# rpi_hat.net
KiCad netlist of a schematic drawn in EAGLE
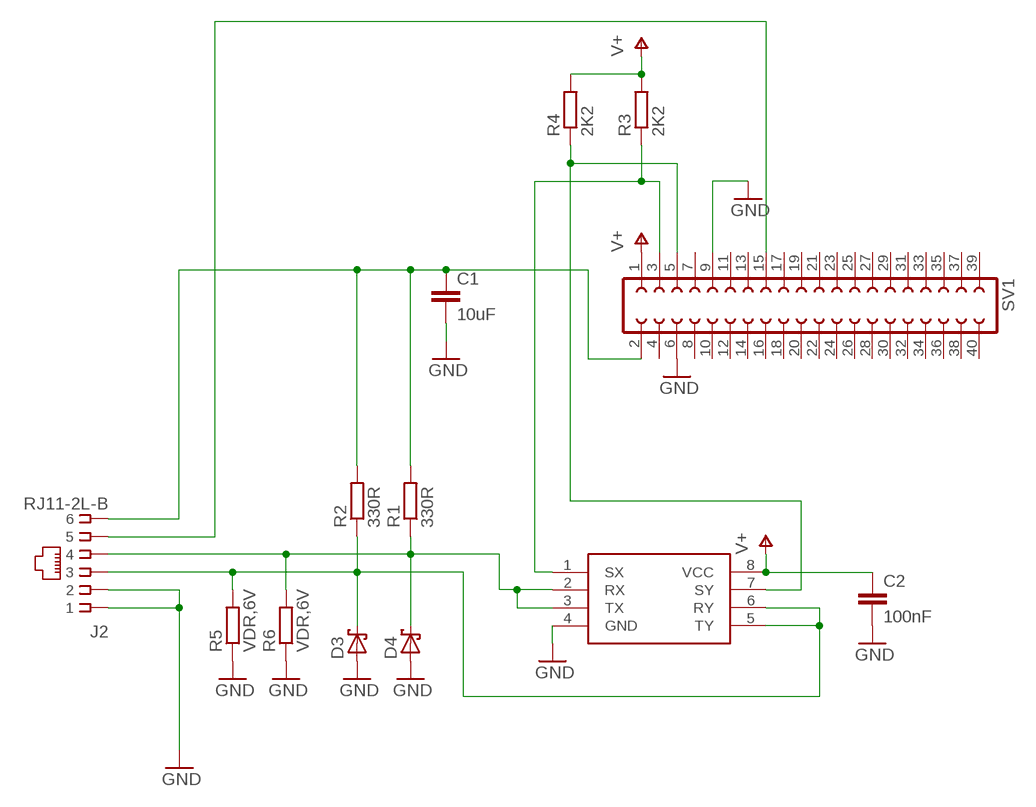
[diagram p0: schematic, sheet 1]

(export (version "E")
  (design (tool "Eeschema 10.0.6"))
  (components
    (comp (ref "C1")
      (value "10uF")
      (footprint "eagle-import:C0805")
      (libsource (lib "eagle-import") (part "C-EUC0805"))
    )
    (comp (ref "C2")
      (value "100nF")
      (footprint "eagle-import:C0805")
      (libsource (lib "eagle-import") (part "C-EUC0805"))
    )
    (comp (ref "D3")
      (value "SCHOTTKY-DIODE")
      (footprint "eagle-import:DIODE_SMB")
      (libsource (lib "eagle-import") (part "SCHOTTKY-DIODE"))
    )
    (comp (ref "D4")
      (value "SCHOTTKY-DIODE")
      (footprint "eagle-import:DIODE_SMB")
      (libsource (lib "eagle-import") (part "SCHOTTKY-DIODE"))
    )
    (comp (ref "J2")
      (value "RJ11-2L-B")
      (footprint "eagle-import:RJ11-NO_SHIELD")
      (fields (field (name "MF") "TYCO ELECTRONICS"))
      (libsource (lib "eagle-import") (part "RJ11-2L-B"))
    )
    (comp (ref "R1")
      (value "330R")
      (footprint "eagle-import:R0805")
      (libsource (lib "eagle-import") (part "R-EU_R0805"))
    )
    (comp (ref "R2")
      (value "330R")
      (footprint "eagle-import:R0805")
      (libsource (lib "eagle-import") (part "R-EU_R0805"))
    )
    (comp (ref "R3")
      (value "2K2")
      (footprint "eagle-import:R0805")
      (libsource (lib "eagle-import") (part "R-EU_R0805"))
    )
    (comp (ref "R4")
      (value "2K2")
      (footprint "eagle-import:R0805")
      (libsource (lib "eagle-import") (part "R-EU_R0805"))
    )
    (comp (ref "R5")
      (value "VDR,6V")
      (footprint "eagle-import:R1206")
      (libsource (lib "eagle-import") (part "R-EU_R1206"))
    )
    (comp (ref "R6")
      (value "VDR,6V")
      (footprint "eagle-import:R1206")
      (libsource (lib "eagle-import") (part "R-EU_R1206"))
    )
    (comp (ref "SV1")
      (value "FE20-2")
      (footprint "eagle-import:FE20-2")
      (libsource (lib "eagle-import") (part "FE20-2"))
    )
    (comp (ref "U$2")
      (value "P82B96")
      (footprint "eagle-import:DIP8")
      (libsource (lib "eagle-import") (part "P82B96"))
    )
  )
  (nets
    (net (code "1") (name "GND") (class "Default")
      (node (ref "C1") (pin "2") (pinfunction "2_2") (pintype "passive"))
      (node (ref "C2") (pin "2") (pinfunction "2_2") (pintype "passive"))
      (node (ref "D3") (pin "A") (pinfunction "C_A") (pintype "passive"))
      (node (ref "D4") (pin "A") (pinfunction "C_A") (pintype "passive"))
      (node (ref "J2") (pin "1") (pinfunction "1_1") (pintype "passive"))
      (node (ref "J2") (pin "2") (pinfunction "2_2") (pintype "passive"))
      (node (ref "R5") (pin "1") (pinfunction "1_1") (pintype "passive"))
      (node (ref "R6") (pin "1") (pinfunction "1_1") (pintype "passive"))
      (node (ref "SV1") (pin "6") (pinfunction "6_6") (pintype "passive"))
      (node (ref "SV1") (pin "9") (pinfunction "9_9") (pintype "passive"))
      (node (ref "U$2") (pin "4") (pinfunction "GND_4") (pintype "bidirectional"))
    )
    (net (code "2") (name "Net-(C1-Pad1)") (class "Default")
      (node (ref "C1") (pin "1") (pinfunction "1_1") (pintype "passive"))
      (node (ref "J2") (pin "6") (pinfunction "6_6") (pintype "passive"))
      (node (ref "R1") (pin "2") (pinfunction "2_2") (pintype "passive"))
      (node (ref "R2") (pin "2") (pinfunction "2_2") (pintype "passive"))
      (node (ref "SV1") (pin "2") (pinfunction "2_2") (pintype "passive"))
    )
    (net (code "3") (name "Net-(D3-A)") (class "Default")
      (node (ref "D3") (pin "C") (pinfunction "A_C") (pintype "passive"))
      (node (ref "J2") (pin "3") (pinfunction "3_3") (pintype "passive"))
      (node (ref "R2") (pin "1") (pinfunction "1_1") (pintype "passive"))
      (node (ref "R5") (pin "2") (pinfunction "2_2") (pintype "passive"))
      (node (ref "U$2") (pin "5") (pinfunction "TY_5") (pintype "bidirectional"))
      (node (ref "U$2") (pin "6") (pinfunction "RY_6") (pintype "bidirectional"))
    )
    (net (code "4") (name "Net-(D4-A)") (class "Default")
      (node (ref "D4") (pin "C") (pinfunction "A_C") (pintype "passive"))
      (node (ref "J2") (pin "4") (pinfunction "4_4") (pintype "passive"))
      (node (ref "R1") (pin "1") (pinfunction "1_1") (pintype "passive"))
      (node (ref "R6") (pin "2") (pinfunction "2_2") (pintype "passive"))
      (node (ref "U$2") (pin "2") (pinfunction "RX_2") (pintype "bidirectional"))
      (node (ref "U$2") (pin "3") (pinfunction "TX_3") (pintype "bidirectional"))
    )
    (net (code "5") (name "Net-(J2-Pad5)") (class "Default")
      (node (ref "J2") (pin "5") (pinfunction "5_5") (pintype "passive"))
      (node (ref "SV1") (pin "15") (pinfunction "15_15") (pintype "passive"))
    )
    (net (code "6") (name "Net-(U$2-SX)") (class "Default")
      (node (ref "R3") (pin "1") (pinfunction "1_1") (pintype "passive"))
      (node (ref "SV1") (pin "3") (pinfunction "3_3") (pintype "passive"))
      (node (ref "U$2") (pin "1") (pinfunction "SX_1") (pintype "bidirectional"))
    )
    (net (code "7") (name "Net-(U$2-SY)") (class "Default")
      (node (ref "R4") (pin "1") (pinfunction "1_1") (pintype "passive"))
      (node (ref "SV1") (pin "5") (pinfunction "5_5") (pintype "passive"))
      (node (ref "U$2") (pin "7") (pinfunction "SY_7") (pintype "bidirectional"))
    )
    (net (code "8") (name "V+") (class "Default")
      (node (ref "C2") (pin "1") (pinfunction "1_1") (pintype "passive"))
      (node (ref "R3") (pin "2") (pinfunction "2_2") (pintype "passive"))
      (node (ref "R4") (pin "2") (pinfunction "2_2") (pintype "passive"))
      (node (ref "SV1") (pin "1") (pinfunction "1_1") (pintype "passive"))
      (node (ref "U$2") (pin "8") (pinfunction "VCC_8") (pintype "bidirectional"))
    )
    (net (code "9") (name "unconnected-(SV1-Pad4)") (class "Default")
      (node (ref "SV1") (pin "4") (pinfunction "4_4") (pintype "passive"))
    )
    (net (code "10") (name "unconnected-(SV1-Pad7)") (class "Default")
      (node (ref "SV1") (pin "7") (pinfunction "7_7") (pintype "passive"))
    )
    (net (code "11") (name "unconnected-(SV1-Pad8)") (class "Default")
      (node (ref "SV1") (pin "8") (pinfunction "8_8") (pintype "passive"))
    )
    (net (code "12") (name "unconnected-(SV1-Pad10)") (class "Default")
      (node (ref "SV1") (pin "10") (pinfunction "10_10") (pintype "passive"))
    )
    (net (code "13") (name "unconnected-(SV1-Pad11)") (class "Default")
      (node (ref "SV1") (pin "11") (pinfunction "11_11") (pintype "passive"))
    )
    (net (code "14") (name "unconnected-(SV1-Pad12)") (class "Default")
      (node (ref "SV1") (pin "12") (pinfunction "12_12") (pintype "passive"))
    )
    (net (code "15") (name "unconnected-(SV1-Pad13)") (class "Default")
      (node (ref "SV1") (pin "13") (pinfunction "13_13") (pintype "passive"))
    )
    (net (code "16") (name "unconnected-(SV1-Pad14)") (class "Default")
      (node (ref "SV1") (pin "14") (pinfunction "14_14") (pintype "passive"))
    )
    (net (code "17") (name "unconnected-(SV1-Pad16)") (class "Default")
      (node (ref "SV1") (pin "16") (pinfunction "16_16") (pintype "passive"))
    )
    (net (code "18") (name "unconnected-(SV1-Pad17)") (class "Default")
      (node (ref "SV1") (pin "17") (pinfunction "17_17") (pintype "passive"))
    )
    (net (code "19") (name "unconnected-(SV1-Pad18)") (class "Default")
      (node (ref "SV1") (pin "18") (pinfunction "18_18") (pintype "passive"))
    )
    (net (code "20") (name "unconnected-(SV1-Pad19)") (class "Default")
      (node (ref "SV1") (pin "19") (pinfunction "19_19") (pintype "passive"))
    )
    (net (code "21") (name "unconnected-(SV1-Pad20)") (class "Default")
      (node (ref "SV1") (pin "20") (pinfunction "20_20") (pintype "passive"))
    )
    (net (code "22") (name "unconnected-(SV1-Pad21)") (class "Default")
      (node (ref "SV1") (pin "21") (pinfunction "21_21") (pintype "passive"))
    )
    (net (code "23") (name "unconnected-(SV1-Pad22)") (class "Default")
      (node (ref "SV1") (pin "22") (pinfunction "22_22") (pintype "passive"))
    )
    (net (code "24") (name "unconnected-(SV1-Pad23)") (class "Default")
      (node (ref "SV1") (pin "23") (pinfunction "23_23") (pintype "passive"))
    )
    (net (code "25") (name "unconnected-(SV1-Pad24)") (class "Default")
      (node (ref "SV1") (pin "24") (pinfunction "24_24") (pintype "passive"))
    )
    (net (code "26") (name "unconnected-(SV1-Pad25)") (class "Default")
      (node (ref "SV1") (pin "25") (pinfunction "25_25") (pintype "passive"))
    )
    (net (code "27") (name "unconnected-(SV1-Pad26)") (class "Default")
      (node (ref "SV1") (pin "26") (pinfunction "26_26") (pintype "passive"))
    )
    (net (code "28") (name "unconnected-(SV1-Pad27)") (class "Default")
      (node (ref "SV1") (pin "27") (pinfunction "27_27") (pintype "passive"))
    )
    (net (code "29") (name "unconnected-(SV1-Pad28)") (class "Default")
      (node (ref "SV1") (pin "28") (pinfunction "28_28") (pintype "passive"))
    )
    (net (code "30") (name "unconnected-(SV1-Pad29)") (class "Default")
      (node (ref "SV1") (pin "29") (pinfunction "29_29") (pintype "passive"))
    )
    (net (code "31") (name "unconnected-(SV1-Pad30)") (class "Default")
      (node (ref "SV1") (pin "30") (pinfunction "30_30") (pintype "passive"))
    )
    (net (code "32") (name "unconnected-(SV1-Pad31)") (class "Default")
      (node (ref "SV1") (pin "31") (pinfunction "31_31") (pintype "passive"))
    )
    (net (code "33") (name "unconnected-(SV1-Pad32)") (class "Default")
      (node (ref "SV1") (pin "32") (pinfunction "32_32") (pintype "passive"))
    )
    (net (code "34") (name "unconnected-(SV1-Pad33)") (class "Default")
      (node (ref "SV1") (pin "33") (pinfunction "33_33") (pintype "passive"))
    )
    (net (code "35") (name "unconnected-(SV1-Pad34)") (class "Default")
      (node (ref "SV1") (pin "34") (pinfunction "34_34") (pintype "passive"))
    )
    (net (code "36") (name "unconnected-(SV1-Pad35)") (class "Default")
      (node (ref "SV1") (pin "35") (pinfunction "35_35") (pintype "passive"))
    )
    (net (code "37") (name "unconnected-(SV1-Pad36)") (class "Default")
      (node (ref "SV1") (pin "36") (pinfunction "36_36") (pintype "passive"))
    )
    (net (code "38") (name "unconnected-(SV1-Pad37)") (class "Default")
      (node (ref "SV1") (pin "37") (pinfunction "37_37") (pintype "passive"))
    )
    (net (code "39") (name "unconnected-(SV1-Pad38)") (class "Default")
      (node (ref "SV1") (pin "38") (pinfunction "38_38") (pintype "passive"))
    )
    (net (code "40") (name "unconnected-(SV1-Pad39)") (class "Default")
      (node (ref "SV1") (pin "39") (pinfunction "39_39") (pintype "passive"))
    )
    (net (code "41") (name "unconnected-(SV1-Pad40)") (class "Default")
      (node (ref "SV1") (pin "40") (pinfunction "40_40") (pintype "passive"))
    )
  )
)
